# Microcontroller.net
KiCad netlist of a schematic drawn in Altium Designer
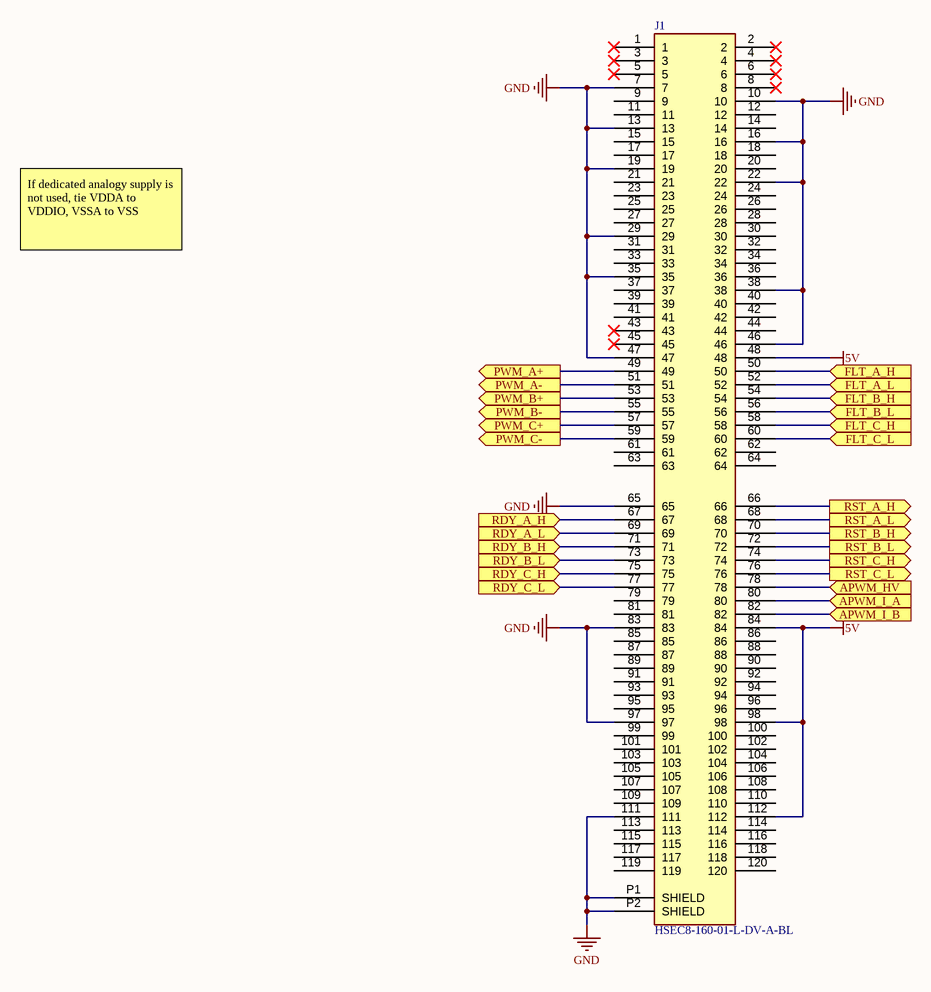
[diagram p0: Microcontroller.SchDoc]

(export (version "E")
  (design (tool "Eeschema 10.0.6"))
  (components
    (comp (ref "J1")
      (value "HSEC8-160-01-L-DV-A-BL")
      (footprint "HSEC8-160-01-L-DV-A-BL:SAMTEC_HSEC8-160-01-L-DV-A-BL")
      (description ".8mm HIGH SPEED DUAL VERTICAL MOUNT EDGE CARD ASSEMBLY")
      (fields (field (name "MF") "{'manufacturer': u'Samtec'}"))
      (libsource (lib "*") (part "HSEC8-160-01-L-DV-A-BL"))
    )
  )
  (nets
    (net (code "1") (name "/APWM_HV") (class "Default")
      (node (ref "J1") (pin "78") (pinfunction "78_78") (pintype "passive"))
    )
    (net (code "2") (name "/APWM_I_A") (class "Default")
      (node (ref "J1") (pin "80") (pinfunction "80_80") (pintype "passive"))
    )
    (net (code "3") (name "/APWM_I_B") (class "Default")
      (node (ref "J1") (pin "82") (pinfunction "82_82") (pintype "passive"))
    )
    (net (code "4") (name "/FLT_A_H") (class "Default")
      (node (ref "J1") (pin "50") (pinfunction "50_50") (pintype "passive"))
    )
    (net (code "5") (name "/FLT_A_L") (class "Default")
      (node (ref "J1") (pin "52") (pinfunction "52_52") (pintype "passive"))
    )
    (net (code "6") (name "/FLT_B_H") (class "Default")
      (node (ref "J1") (pin "54") (pinfunction "54_54") (pintype "passive"))
    )
    (net (code "7") (name "/FLT_B_L") (class "Default")
      (node (ref "J1") (pin "56") (pinfunction "56_56") (pintype "passive"))
    )
    (net (code "8") (name "/FLT_C_H") (class "Default")
      (node (ref "J1") (pin "58") (pinfunction "58_58") (pintype "passive"))
    )
    (net (code "9") (name "/FLT_C_L") (class "Default")
      (node (ref "J1") (pin "60") (pinfunction "60_60") (pintype "passive"))
    )
    (net (code "10") (name "/PWM_A+") (class "Default")
      (node (ref "J1") (pin "49") (pinfunction "49_49") (pintype "passive"))
    )
    (net (code "11") (name "/PWM_A-") (class "Default")
      (node (ref "J1") (pin "51") (pinfunction "51_51") (pintype "passive"))
    )
    (net (code "12") (name "/PWM_B+") (class "Default")
      (node (ref "J1") (pin "53") (pinfunction "53_53") (pintype "passive"))
    )
    (net (code "13") (name "/PWM_B-") (class "Default")
      (node (ref "J1") (pin "55") (pinfunction "55_55") (pintype "passive"))
    )
    (net (code "14") (name "/PWM_C+") (class "Default")
      (node (ref "J1") (pin "57") (pinfunction "57_57") (pintype "passive"))
    )
    (net (code "15") (name "/PWM_C-") (class "Default")
      (node (ref "J1") (pin "59") (pinfunction "59_59") (pintype "passive"))
    )
    (net (code "16") (name "/RDY_A_H") (class "Default")
      (node (ref "J1") (pin "67") (pinfunction "67_67") (pintype "passive"))
    )
    (net (code "17") (name "/RDY_A_L") (class "Default")
      (node (ref "J1") (pin "69") (pinfunction "69_69") (pintype "passive"))
    )
    (net (code "18") (name "/RDY_B_H") (class "Default")
      (node (ref "J1") (pin "71") (pinfunction "71_71") (pintype "passive"))
    )
    (net (code "19") (name "/RDY_B_L") (class "Default")
      (node (ref "J1") (pin "73") (pinfunction "73_73") (pintype "passive"))
    )
    (net (code "20") (name "/RDY_C_H") (class "Default")
      (node (ref "J1") (pin "75") (pinfunction "75_75") (pintype "passive"))
    )
    (net (code "21") (name "/RDY_C_L") (class "Default")
      (node (ref "J1") (pin "77") (pinfunction "77_77") (pintype "passive"))
    )
    (net (code "22") (name "/RST_A_H") (class "Default")
      (node (ref "J1") (pin "66") (pinfunction "66_66") (pintype "passive"))
    )
    (net (code "23") (name "/RST_A_L") (class "Default")
      (node (ref "J1") (pin "68") (pinfunction "68_68") (pintype "passive"))
    )
    (net (code "24") (name "/RST_B_H") (class "Default")
      (node (ref "J1") (pin "70") (pinfunction "70_70") (pintype "passive"))
    )
    (net (code "25") (name "/RST_B_L") (class "Default")
      (node (ref "J1") (pin "72") (pinfunction "72_72") (pintype "passive"))
    )
    (net (code "26") (name "/RST_C_H") (class "Default")
      (node (ref "J1") (pin "74") (pinfunction "74_74") (pintype "passive"))
    )
    (net (code "27") (name "/RST_C_L") (class "Default")
      (node (ref "J1") (pin "76") (pinfunction "76_76") (pintype "passive"))
    )
    (net (code "28") (name "5V") (class "Default")
      (node (ref "J1") (pin "112") (pinfunction "112_112") (pintype "passive"))
      (node (ref "J1") (pin "48") (pinfunction "48_48") (pintype "passive"))
      (node (ref "J1") (pin "84") (pinfunction "84_84") (pintype "passive"))
      (node (ref "J1") (pin "98") (pinfunction "98_98") (pintype "passive"))
    )
    (net (code "29") (name "GND") (class "Default")
      (node (ref "J1") (pin "10") (pinfunction "10_10") (pintype "passive"))
      (node (ref "J1") (pin "111") (pinfunction "111_111") (pintype "passive"))
      (node (ref "J1") (pin "13") (pinfunction "13_13") (pintype "passive"))
      (node (ref "J1") (pin "16") (pinfunction "16_16") (pintype "passive"))
      (node (ref "J1") (pin "19") (pinfunction "19_19") (pintype "passive"))
      (node (ref "J1") (pin "22") (pinfunction "22_22") (pintype "passive"))
      (node (ref "J1") (pin "29") (pinfunction "29_29") (pintype "passive"))
      (node (ref "J1") (pin "35") (pinfunction "35_35") (pintype "passive"))
      (node (ref "J1") (pin "38") (pinfunction "38_38") (pintype "passive"))
      (node (ref "J1") (pin "46") (pinfunction "46_46") (pintype "passive"))
      (node (ref "J1") (pin "47") (pinfunction "47_47") (pintype "passive"))
      (node (ref "J1") (pin "65") (pinfunction "65_65") (pintype "passive"))
      (node (ref "J1") (pin "7") (pinfunction "7_7") (pintype "passive"))
      (node (ref "J1") (pin "83") (pinfunction "83_83") (pintype "passive"))
      (node (ref "J1") (pin "97") (pinfunction "97_97") (pintype "passive"))
      (node (ref "J1") (pin "P1") (pinfunction "SHIELD_P1") (pintype "passive"))
      (node (ref "J1") (pin "P2") (pinfunction "SHIELD_P2") (pintype "passive"))
    )
    (net (code "30") (name "unconnected-(J1-Pad1)") (class "Default")
      (node (ref "J1") (pin "1") (pinfunction "1_1") (pintype "passive+no_connect"))
    )
    (net (code "31") (name "unconnected-(J1-Pad2)") (class "Default")
      (node (ref "J1") (pin "2") (pinfunction "2_2") (pintype "passive+no_connect"))
    )
    (net (code "32") (name "unconnected-(J1-Pad3)") (class "Default")
      (node (ref "J1") (pin "3") (pinfunction "3_3") (pintype "passive+no_connect"))
    )
    (net (code "33") (name "unconnected-(J1-Pad4)") (class "Default")
      (node (ref "J1") (pin "4") (pinfunction "4_4") (pintype "passive+no_connect"))
    )
    (net (code "34") (name "unconnected-(J1-Pad5)") (class "Default")
      (node (ref "J1") (pin "5") (pinfunction "5_5") (pintype "passive+no_connect"))
    )
    (net (code "35") (name "unconnected-(J1-Pad6)") (class "Default")
      (node (ref "J1") (pin "6") (pinfunction "6_6") (pintype "passive+no_connect"))
    )
    (net (code "36") (name "unconnected-(J1-Pad8)") (class "Default")
      (node (ref "J1") (pin "8") (pinfunction "8_8") (pintype "passive+no_connect"))
    )
    (net (code "37") (name "unconnected-(J1-Pad9)") (class "Default")
      (node (ref "J1") (pin "9") (pinfunction "9_9") (pintype "passive"))
    )
    (net (code "38") (name "unconnected-(J1-Pad11)") (class "Default")
      (node (ref "J1") (pin "11") (pinfunction "11_11") (pintype "passive"))
    )
    (net (code "39") (name "unconnected-(J1-Pad12)") (class "Default")
      (node (ref "J1") (pin "12") (pinfunction "12_12") (pintype "passive"))
    )
    (net (code "40") (name "unconnected-(J1-Pad14)") (class "Default")
      (node (ref "J1") (pin "14") (pinfunction "14_14") (pintype "passive"))
    )
    (net (code "41") (name "unconnected-(J1-Pad15)") (class "Default")
      (node (ref "J1") (pin "15") (pinfunction "15_15") (pintype "passive"))
    )
    (net (code "42") (name "unconnected-(J1-Pad17)") (class "Default")
      (node (ref "J1") (pin "17") (pinfunction "17_17") (pintype "passive"))
    )
    (net (code "43") (name "unconnected-(J1-Pad18)") (class "Default")
      (node (ref "J1") (pin "18") (pinfunction "18_18") (pintype "passive"))
    )
    (net (code "44") (name "unconnected-(J1-Pad20)") (class "Default")
      (node (ref "J1") (pin "20") (pinfunction "20_20") (pintype "passive"))
    )
    (net (code "45") (name "unconnected-(J1-Pad21)") (class "Default")
      (node (ref "J1") (pin "21") (pinfunction "21_21") (pintype "passive"))
    )
    (net (code "46") (name "unconnected-(J1-Pad23)") (class "Default")
      (node (ref "J1") (pin "23") (pinfunction "23_23") (pintype "passive"))
    )
    (net (code "47") (name "unconnected-(J1-Pad24)") (class "Default")
      (node (ref "J1") (pin "24") (pinfunction "24_24") (pintype "passive"))
    )
    (net (code "48") (name "unconnected-(J1-Pad25)") (class "Default")
      (node (ref "J1") (pin "25") (pinfunction "25_25") (pintype "passive"))
    )
    (net (code "49") (name "unconnected-(J1-Pad26)") (class "Default")
      (node (ref "J1") (pin "26") (pinfunction "26_26") (pintype "passive"))
    )
    (net (code "50") (name "unconnected-(J1-Pad27)") (class "Default")
      (node (ref "J1") (pin "27") (pinfunction "27_27") (pintype "passive"))
    )
    (net (code "51") (name "unconnected-(J1-Pad28)") (class "Default")
      (node (ref "J1") (pin "28") (pinfunction "28_28") (pintype "passive"))
    )
    (net (code "52") (name "unconnected-(J1-Pad30)") (class "Default")
      (node (ref "J1") (pin "30") (pinfunction "30_30") (pintype "passive"))
    )
    (net (code "53") (name "unconnected-(J1-Pad31)") (class "Default")
      (node (ref "J1") (pin "31") (pinfunction "31_31") (pintype "passive"))
    )
    (net (code "54") (name "unconnected-(J1-Pad32)") (class "Default")
      (node (ref "J1") (pin "32") (pinfunction "32_32") (pintype "passive"))
    )
    (net (code "55") (name "unconnected-(J1-Pad33)") (class "Default")
      (node (ref "J1") (pin "33") (pinfunction "33_33") (pintype "passive"))
    )
    (net (code "56") (name "unconnected-(J1-Pad34)") (class "Default")
      (node (ref "J1") (pin "34") (pinfunction "34_34") (pintype "passive"))
    )
    (net (code "57") (name "unconnected-(J1-Pad36)") (class "Default")
      (node (ref "J1") (pin "36") (pinfunction "36_36") (pintype "passive"))
    )
    (net (code "58") (name "unconnected-(J1-Pad37)") (class "Default")
      (node (ref "J1") (pin "37") (pinfunction "37_37") (pintype "passive"))
    )
    (net (code "59") (name "unconnected-(J1-Pad39)") (class "Default")
      (node (ref "J1") (pin "39") (pinfunction "39_39") (pintype "passive"))
    )
    (net (code "60") (name "unconnected-(J1-Pad40)") (class "Default")
      (node (ref "J1") (pin "40") (pinfunction "40_40") (pintype "passive"))
    )
    (net (code "61") (name "unconnected-(J1-Pad41)") (class "Default")
      (node (ref "J1") (pin "41") (pinfunction "41_41") (pintype "passive"))
    )
    (net (code "62") (name "unconnected-(J1-Pad42)") (class "Default")
      (node (ref "J1") (pin "42") (pinfunction "42_42") (pintype "passive"))
    )
    (net (code "63") (name "unconnected-(J1-Pad43)") (class "Default")
      (node (ref "J1") (pin "43") (pinfunction "43_43") (pintype "passive+no_connect"))
    )
    (net (code "64") (name "unconnected-(J1-Pad44)") (class "Default")
      (node (ref "J1") (pin "44") (pinfunction "44_44") (pintype "passive"))
    )
    (net (code "65") (name "unconnected-(J1-Pad45)") (class "Default")
      (node (ref "J1") (pin "45") (pinfunction "45_45") (pintype "passive+no_connect"))
    )
    (net (code "66") (name "unconnected-(J1-Pad61)") (class "Default")
      (node (ref "J1") (pin "61") (pinfunction "61_61") (pintype "passive"))
    )
    (net (code "67") (name "unconnected-(J1-Pad62)") (class "Default")
      (node (ref "J1") (pin "62") (pinfunction "62_62") (pintype "passive"))
    )
    (net (code "68") (name "unconnected-(J1-Pad63)") (class "Default")
      (node (ref "J1") (pin "63") (pinfunction "63_63") (pintype "passive"))
    )
    (net (code "69") (name "unconnected-(J1-Pad64)") (class "Default")
      (node (ref "J1") (pin "64") (pinfunction "64_64") (pintype "passive"))
    )
    (net (code "70") (name "unconnected-(J1-Pad79)") (class "Default")
      (node (ref "J1") (pin "79") (pinfunction "79_79") (pintype "passive"))
    )
    (net (code "71") (name "unconnected-(J1-Pad81)") (class "Default")
      (node (ref "J1") (pin "81") (pinfunction "81_81") (pintype "passive"))
    )
    (net (code "72") (name "unconnected-(J1-Pad85)") (class "Default")
      (node (ref "J1") (pin "85") (pinfunction "85_85") (pintype "passive"))
    )
    (net (code "73") (name "unconnected-(J1-Pad86)") (class "Default")
      (node (ref "J1") (pin "86") (pinfunction "86_86") (pintype "passive"))
    )
    (net (code "74") (name "unconnected-(J1-Pad87)") (class "Default")
      (node (ref "J1") (pin "87") (pinfunction "87_87") (pintype "passive"))
    )
    (net (code "75") (name "unconnected-(J1-Pad88)") (class "Default")
      (node (ref "J1") (pin "88") (pinfunction "88_88") (pintype "passive"))
    )
    (net (code "76") (name "unconnected-(J1-Pad89)") (class "Default")
      (node (ref "J1") (pin "89") (pinfunction "89_89") (pintype "passive"))
    )
    (net (code "77") (name "unconnected-(J1-Pad90)") (class "Default")
      (node (ref "J1") (pin "90") (pinfunction "90_90") (pintype "passive"))
    )
    (net (code "78") (name "unconnected-(J1-Pad91)") (class "Default")
      (node (ref "J1") (pin "91") (pinfunction "91_91") (pintype "passive"))
    )
    (net (code "79") (name "unconnected-(J1-Pad92)") (class "Default")
      (node (ref "J1") (pin "92") (pinfunction "92_92") (pintype "passive"))
    )
    (net (code "80") (name "unconnected-(J1-Pad93)") (class "Default")
      (node (ref "J1") (pin "93") (pinfunction "93_93") (pintype "passive"))
    )
    (net (code "81") (name "unconnected-(J1-Pad94)") (class "Default")
      (node (ref "J1") (pin "94") (pinfunction "94_94") (pintype "passive"))
    )
    (net (code "82") (name "unconnected-(J1-Pad95)") (class "Default")
      (node (ref "J1") (pin "95") (pinfunction "95_95") (pintype "passive"))
    )
    (net (code "83") (name "unconnected-(J1-Pad96)") (class "Default")
      (node (ref "J1") (pin "96") (pinfunction "96_96") (pintype "passive"))
    )
    (net (code "84") (name "unconnected-(J1-Pad99)") (class "Default")
      (node (ref "J1") (pin "99") (pinfunction "99_99") (pintype "passive"))
    )
    (net (code "85") (name "unconnected-(J1-Pad100)") (class "Default")
      (node (ref "J1") (pin "100") (pinfunction "100_100") (pintype "passive"))
    )
    (net (code "86") (name "unconnected-(J1-Pad101)") (class "Default")
      (node (ref "J1") (pin "101") (pinfunction "101_101") (pintype "passive"))
    )
    (net (code "87") (name "unconnected-(J1-Pad102)") (class "Default")
      (node (ref "J1") (pin "102") (pinfunction "102_102") (pintype "passive"))
    )
    (net (code "88") (name "unconnected-(J1-Pad103)") (class "Default")
      (node (ref "J1") (pin "103") (pinfunction "103_103") (pintype "passive"))
    )
    (net (code "89") (name "unconnected-(J1-Pad104)") (class "Default")
      (node (ref "J1") (pin "104") (pinfunction "104_104") (pintype "passive"))
    )
    (net (code "90") (name "unconnected-(J1-Pad105)") (class "Default")
      (node (ref "J1") (pin "105") (pinfunction "105_105") (pintype "passive"))
    )
    (net (code "91") (name "unconnected-(J1-Pad106)") (class "Default")
      (node (ref "J1") (pin "106") (pinfunction "106_106") (pintype "passive"))
    )
    (net (code "92") (name "unconnected-(J1-Pad107)") (class "Default")
      (node (ref "J1") (pin "107") (pinfunction "107_107") (pintype "passive"))
    )
    (net (code "93") (name "unconnected-(J1-Pad108)") (class "Default")
      (node (ref "J1") (pin "108") (pinfunction "108_108") (pintype "passive"))
    )
    (net (code "94") (name "unconnected-(J1-Pad109)") (class "Default")
      (node (ref "J1") (pin "109") (pinfunction "109_109") (pintype "passive"))
    )
    (net (code "95") (name "unconnected-(J1-Pad110)") (class "Default")
      (node (ref "J1") (pin "110") (pinfunction "110_110") (pintype "passive"))
    )
    (net (code "96") (name "unconnected-(J1-Pad113)") (class "Default")
      (node (ref "J1") (pin "113") (pinfunction "113_113") (pintype "passive"))
    )
    (net (code "97") (name "unconnected-(J1-Pad114)") (class "Default")
      (node (ref "J1") (pin "114") (pinfunction "114_114") (pintype "passive"))
    )
    (net (code "98") (name "unconnected-(J1-Pad115)") (class "Default")
      (node (ref "J1") (pin "115") (pinfunction "115_115") (pintype "passive"))
    )
    (net (code "99") (name "unconnected-(J1-Pad116)") (class "Default")
      (node (ref "J1") (pin "116") (pinfunction "116_116") (pintype "passive"))
    )
    (net (code "100") (name "unconnected-(J1-Pad117)") (class "Default")
      (node (ref "J1") (pin "117") (pinfunction "117_117") (pintype "passive"))
    )
    (net (code "101") (name "unconnected-(J1-Pad118)") (class "Default")
      (node (ref "J1") (pin "118") (pinfunction "118_118") (pintype "passive"))
    )
    (net (code "102") (name "unconnected-(J1-Pad119)") (class "Default")
      (node (ref "J1") (pin "119") (pinfunction "119_119") (pintype "passive"))
    )
    (net (code "103") (name "unconnected-(J1-Pad120)") (class "Default")
      (node (ref "J1") (pin "120") (pinfunction "120_120") (pintype "passive"))
    )
  )
)
